# LP-measurment_v15.net
KiCad netlist of a schematic drawn in EAGLE
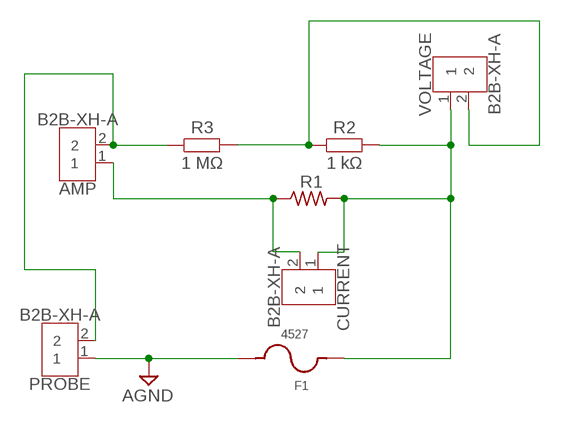
[diagram p0: schematic, sheet 1]

(export (version "E")
  (design (tool "Eeschema 10.0.6"))
  (components
    (comp (ref "AMP")
      (value "B2B-XH-A")
      (footprint "eagle-import:B2B-XH-A")
      (fields (field (name "MANUFACTURER") "JST Sales America Inc."))
      (libsource (lib "eagle-import") (part "B2B-XH-A"))
    )
    (comp (ref "CURRENT")
      (value "B2B-XH-A")
      (footprint "eagle-import:B2B-XH-A")
      (fields (field (name "MANUFACTURER") "JST Sales America Inc."))
      (libsource (lib "eagle-import") (part "B2B-XH-A"))
    )
    (comp (ref "F1")
      (value "4527")
      (footprint "eagle-import:4527")
      (fields
        (field (name "MANUFACTURER") "Keystone Electronics")
        (field (name "CREATED_BY") "PCBLayout.com")
      )
      (libsource (lib "eagle-import") (part "4527"))
    )
    (comp (ref "PROBE")
      (value "B2B-XH-A")
      (footprint "eagle-import:B2B-XH-A")
      (fields (field (name "MANUFACTURER") "JST Sales America Inc."))
      (libsource (lib "eagle-import") (part "B2B-XH-A"))
    )
    (comp (ref "R1")
      (value "R-US_0817/22")
      (footprint "eagle-import:P0817_22")
      (libsource (lib "eagle-import") (part "R-US_0817/22"))
    )
    (comp (ref "R2")
      (value "1 kΩ")
      (footprint "eagle-import:RESAD1176W63L850D250B")
      (libsource (lib "eagle-import") (part "RAXIAL-11.7MM-PITCH_"))
    )
    (comp (ref "R3")
      (value "1 MΩ")
      (footprint "eagle-import:RESAD1176W63L850D250B")
      (libsource (lib "eagle-import") (part "RAXIAL-11.7MM-PITCH_"))
    )
    (comp (ref "VOLTAGE")
      (value "B2B-XH-A")
      (footprint "eagle-import:B2B-XH-A")
      (fields (field (name "MANUFACTURER") "JST Sales America Inc."))
      (libsource (lib "eagle-import") (part "B2B-XH-A"))
    )
  )
  (nets
    (net (code "1") (name "AGND") (class "Default")
      (node (ref "F1") (pin "2") (pinfunction "2_2") (pintype "passive"))
      (node (ref "PROBE") (pin "1") (pinfunction "1_1") (pintype "bidirectional"))
    )
    (net (code "2") (name "Net-(AMP-Pad1)") (class "Default")
      (node (ref "AMP") (pin "1") (pinfunction "1_1") (pintype "bidirectional"))
      (node (ref "CURRENT") (pin "2") (pinfunction "2_2") (pintype "bidirectional"))
      (node (ref "R1") (pin "1") (pinfunction "1_1") (pintype "passive"))
    )
    (net (code "3") (name "Net-(AMP-Pad2)") (class "Default")
      (node (ref "AMP") (pin "2") (pinfunction "2_2") (pintype "bidirectional"))
      (node (ref "PROBE") (pin "2") (pinfunction "2_2") (pintype "bidirectional"))
      (node (ref "R3") (pin "1") (pinfunction "1_1") (pintype "passive"))
    )
    (net (code "4") (name "Net-(CURRENT-Pad1)") (class "Default")
      (node (ref "CURRENT") (pin "1") (pinfunction "1_1") (pintype "bidirectional"))
      (node (ref "F1") (pin "1") (pinfunction "1_1") (pintype "passive"))
      (node (ref "R1") (pin "2") (pinfunction "2_2") (pintype "passive"))
      (node (ref "R2") (pin "2") (pinfunction "2_2") (pintype "passive"))
      (node (ref "VOLTAGE") (pin "1") (pinfunction "1_1") (pintype "bidirectional"))
    )
    (net (code "5") (name "Net-(R2-Pad1)") (class "Default")
      (node (ref "R2") (pin "1") (pinfunction "1_1") (pintype "passive"))
      (node (ref "R3") (pin "2") (pinfunction "2_2") (pintype "passive"))
      (node (ref "VOLTAGE") (pin "2") (pinfunction "2_2") (pintype "bidirectional"))
    )
  )
)
